# icl7107pins.net
KiCad netlist of a schematic drawn in Altium Designer
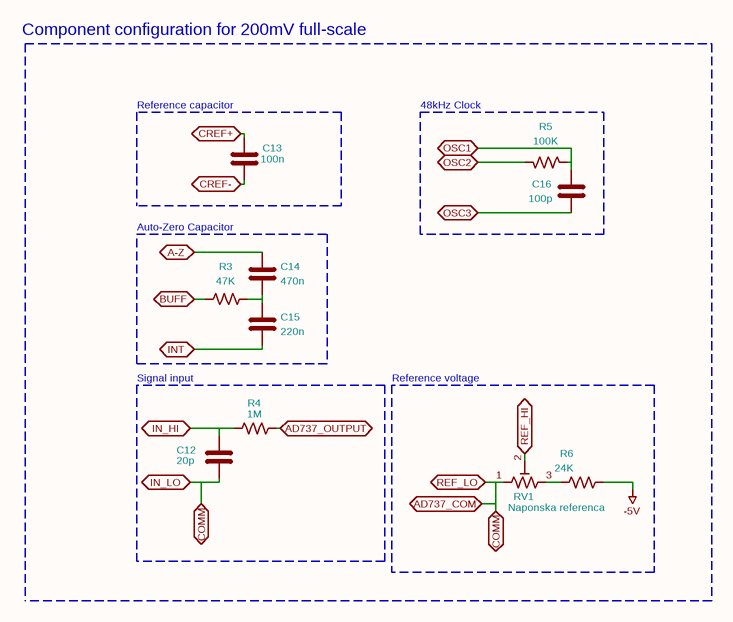
[diagram p0: icl7107pins.SchDoc]

(export (version "E")
  (design (tool "Eeschema 10.0.6"))
  (components
    (comp (ref "C12") (value "20p") (libsource (lib "Device") (part "C")))
    (comp (ref "C13") (value "100n") (libsource (lib "Device") (part "C")))
    (comp (ref "C14") (value "470n") (libsource (lib "Device") (part "C")))
    (comp (ref "C15") (value "220n") (libsource (lib "Device") (part "C")))
    (comp (ref "C16") (value "100p") (libsource (lib "Device") (part "C")))
    (comp (ref "R3") (value "47K") (libsource (lib "Device") (part "R_US")))
    (comp (ref "R4") (value "1M") (libsource (lib "Device") (part "R_US")))
    (comp (ref "R5") (value "100K") (libsource (lib "Device") (part "R_US")))
    (comp (ref "R6") (value "24K") (libsource (lib "Device") (part "R_US")))
    (comp (ref "RV1")
      (value "Naponska referenca")
      (libsource (lib "Device") (part "R_Potentiometer_Trim_US"))
    )
  )
  (nets
    (net (code "1") (name "-5V") (class "Default")
      (node (ref "R6") (pin "1") (pinfunction "1_1") (pintype "passive"))
    )
    (net (code "2") (name "/A-Z") (class "Default")
      (node (ref "C14") (pin "2") (pinfunction "2_2") (pintype "passive"))
    )
    (net (code "3") (name "/AD737_COM") (class "Default")
      (node (ref "C12") (pin "2") (pinfunction "2_2") (pintype "passive"))
      (node (ref "RV1") (pin "1") (pinfunction "1_1") (pintype "passive"))
    )
    (net (code "4") (name "/AD737_OUTPUT") (class "Default")
      (node (ref "R4") (pin "2") (pinfunction "2_2") (pintype "passive"))
    )
    (net (code "5") (name "/BUFF") (class "Default")
      (node (ref "R3") (pin "1") (pinfunction "1_1") (pintype "passive"))
    )
    (net (code "6") (name "/CREF+") (class "Default")
      (node (ref "C13") (pin "1") (pinfunction "1_1") (pintype "passive"))
    )
    (net (code "7") (name "/CREF-") (class "Default")
      (node (ref "C13") (pin "2") (pinfunction "2_2") (pintype "passive"))
    )
    (net (code "8") (name "/INT") (class "Default")
      (node (ref "C15") (pin "1") (pinfunction "1_1") (pintype "passive"))
    )
    (net (code "9") (name "/IN_HI") (class "Default")
      (node (ref "C12") (pin "1") (pinfunction "1_1") (pintype "passive"))
      (node (ref "R4") (pin "1") (pinfunction "1_1") (pintype "passive"))
    )
    (net (code "10") (name "/OSC1") (class "Default")
      (node (ref "C16") (pin "1") (pinfunction "1_1") (pintype "passive"))
      (node (ref "R5") (pin "1") (pinfunction "1_1") (pintype "passive"))
    )
    (net (code "11") (name "/OSC2") (class "Default")
      (node (ref "R5") (pin "2") (pinfunction "2_2") (pintype "passive"))
    )
    (net (code "12") (name "/OSC3") (class "Default")
      (node (ref "C16") (pin "2") (pinfunction "2_2") (pintype "passive"))
    )
    (net (code "13") (name "/REF_HI") (class "Default")
      (node (ref "RV1") (pin "2") (pinfunction "2_2") (pintype "passive"))
    )
    (net (code "14") (name "Net-(C14-Pad1)") (class "Default")
      (node (ref "C14") (pin "1") (pinfunction "1_1") (pintype "passive"))
      (node (ref "C15") (pin "2") (pinfunction "2_2") (pintype "passive"))
      (node (ref "R3") (pin "2") (pinfunction "2_2") (pintype "passive"))
    )
    (net (code "15") (name "Net-(R6-Pad2)") (class "Default")
      (node (ref "R6") (pin "2") (pinfunction "2_2") (pintype "passive"))
      (node (ref "RV1") (pin "3") (pinfunction "3_3") (pintype "passive"))
    )
  )
)
